# charger.net
KiCad netlist of a schematic drawn in EAGLE
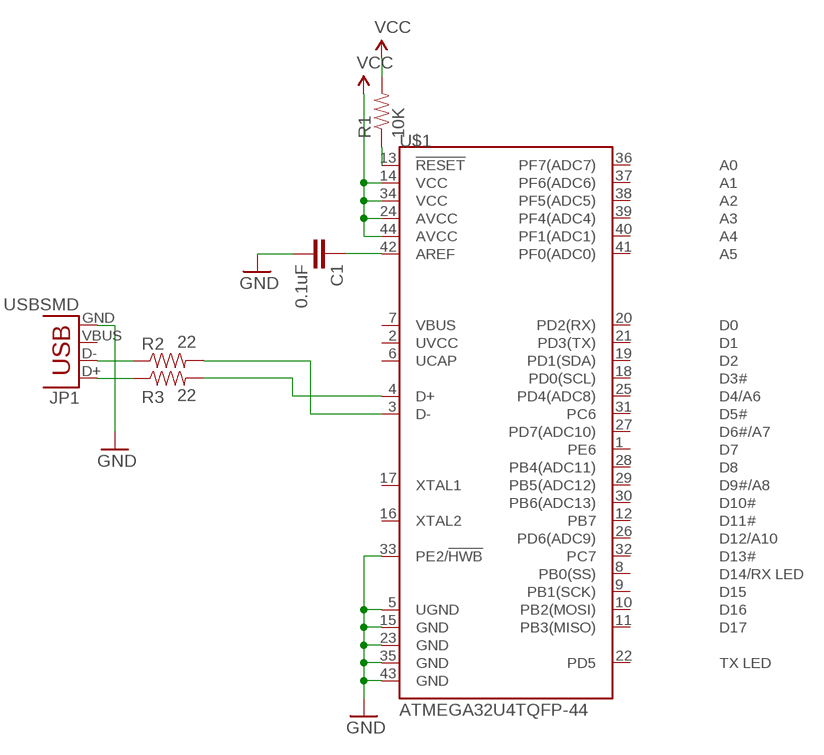
[diagram p0: schematic, sheet 1]

(export (version "E")
  (design (tool "Eeschema 10.0.6"))
  (components
    (comp (ref "C1")
      (value "0.1uF")
      (footprint "eagle-import:0603-CAP")
      (libsource (lib "eagle-import") (part "0.1UF-25V(+80/-20%)(0603)"))
    )
    (comp (ref "JP1")
      (value "USBSMD")
      (footprint "eagle-import:USB-MINIB")
      (libsource (lib "eagle-import") (part "USBSMD"))
    )
    (comp (ref "R1")
      (value "10K")
      (footprint "eagle-import:0603-RES")
      (libsource (lib "eagle-import") (part "10KOHM-1/10W-1%(0603)0603"))
    )
    (comp (ref "R2")
      (value "22")
      (footprint "eagle-import:0603-RES")
      (libsource (lib "eagle-import") (part "22OHM1/10W1%(0603)"))
    )
    (comp (ref "R3")
      (value "22")
      (footprint "eagle-import:0603-RES")
      (libsource (lib "eagle-import") (part "22OHM1/10W1%(0603)"))
    )
    (comp (ref "U$1")
      (value "ATMEGA32U4TQFP-44")
      (footprint "eagle-import:TQFP44")
      (libsource (lib "eagle-import") (part "ATMEGA32U4TQFP-44"))
    )
  )
  (nets
    (net (code "1") (name "GND") (class "Default")
      (node (ref "C1") (pin "2") (pinfunction "2_2") (pintype "passive"))
      (node (ref "JP1") (pin "GND") (pinfunction "GND_GND") (pintype "bidirectional"))
      (node (ref "U$1") (pin "15") (pinfunction "GND_15") (pintype "bidirectional"))
      (node (ref "U$1") (pin "23") (pinfunction "GND_23") (pintype "bidirectional"))
      (node (ref "U$1") (pin "33") (pinfunction "PE2/~{HWB}_33") (pintype "bidirectional"))
      (node (ref "U$1") (pin "35") (pinfunction "GND_35") (pintype "bidirectional"))
      (node (ref "U$1") (pin "43") (pinfunction "GND_43") (pintype "bidirectional"))
      (node (ref "U$1") (pin "5") (pinfunction "UGND_5") (pintype "bidirectional"))
    )
    (net (code "2") (name "Net-(JP1-PadD+)") (class "Default")
      (node (ref "JP1") (pin "D+") (pinfunction "D+_D+") (pintype "bidirectional"))
      (node (ref "R3") (pin "1") (pinfunction "1_1") (pintype "passive"))
    )
    (net (code "3") (name "Net-(JP1-PadD-)") (class "Default")
      (node (ref "JP1") (pin "D-") (pinfunction "D-_D-") (pintype "bidirectional"))
      (node (ref "R2") (pin "1") (pinfunction "1_1") (pintype "passive"))
    )
    (net (code "4") (name "Net-(U$1-AREF)") (class "Default")
      (node (ref "C1") (pin "1") (pinfunction "1_1") (pintype "passive"))
      (node (ref "U$1") (pin "42") (pinfunction "AREF_42") (pintype "bidirectional"))
    )
    (net (code "5") (name "Net-(U$1-D+)") (class "Default")
      (node (ref "R3") (pin "2") (pinfunction "2_2") (pintype "passive"))
      (node (ref "U$1") (pin "4") (pinfunction "D+_4") (pintype "bidirectional"))
    )
    (net (code "6") (name "Net-(U$1-D-)") (class "Default")
      (node (ref "R2") (pin "2") (pinfunction "2_2") (pintype "passive"))
      (node (ref "U$1") (pin "3") (pinfunction "D-_3") (pintype "bidirectional"))
    )
    (net (code "7") (name "Net-(U$1-~{RESET})") (class "Default")
      (node (ref "R1") (pin "1") (pinfunction "1_1") (pintype "passive"))
      (node (ref "U$1") (pin "13") (pinfunction "~{RESET}_13") (pintype "bidirectional"))
    )
    (net (code "8") (name "VCC") (class "Default")
      (node (ref "R1") (pin "2") (pinfunction "2_2") (pintype "passive"))
      (node (ref "U$1") (pin "14") (pinfunction "VCC_14") (pintype "bidirectional"))
      (node (ref "U$1") (pin "24") (pinfunction "AVCC_24") (pintype "bidirectional"))
      (node (ref "U$1") (pin "34") (pinfunction "VCC_34") (pintype "bidirectional"))
      (node (ref "U$1") (pin "44") (pinfunction "AVCC_44") (pintype "bidirectional"))
    )
    (net (code "9") (name "unconnected-(JP1-PadVBUS)") (class "Default")
      (node (ref "JP1") (pin "VBUS") (pinfunction "VBUS_VBUS") (pintype "bidirectional"))
    )
    (net (code "10") (name "unconnected-(U$1-PB0(SS)-Pad8)") (class "Default")
      (node (ref "U$1") (pin "8") (pinfunction "PB0(SS)_8") (pintype "bidirectional"))
    )
    (net (code "11") (name "unconnected-(U$1-PB1(SCK)-Pad9)") (class "Default")
      (node (ref "U$1") (pin "9") (pinfunction "PB1(SCK)_9") (pintype "bidirectional"))
    )
    (net (code "12") (name "unconnected-(U$1-PB2(MOSI)-Pad10)") (class "Default")
      (node (ref "U$1") (pin "10") (pinfunction "PB2(MOSI)_10") (pintype "bidirectional"))
    )
    (net (code "13") (name "unconnected-(U$1-PB3(MISO)-Pad11)") (class "Default")
      (node (ref "U$1") (pin "11") (pinfunction "PB3(MISO)_11") (pintype "bidirectional"))
    )
    (net (code "14") (name "unconnected-(U$1-PB4(ADC11)-Pad28)") (class "Default")
      (node (ref "U$1") (pin "28") (pinfunction "PB4(ADC11)_28") (pintype "bidirectional"))
    )
    (net (code "15") (name "unconnected-(U$1-PB5(ADC12)-Pad29)") (class "Default")
      (node (ref "U$1") (pin "29") (pinfunction "PB5(ADC12)_29") (pintype "bidirectional"))
    )
    (net (code "16") (name "unconnected-(U$1-PB6(ADC13)-Pad30)") (class "Default")
      (node (ref "U$1") (pin "30") (pinfunction "PB6(ADC13)_30") (pintype "bidirectional"))
    )
    (net (code "17") (name "unconnected-(U$1-PB7-Pad12)") (class "Default")
      (node (ref "U$1") (pin "12") (pinfunction "PB7_12") (pintype "bidirectional"))
    )
    (net (code "18") (name "unconnected-(U$1-PC6-Pad31)") (class "Default")
      (node (ref "U$1") (pin "31") (pinfunction "PC6_31") (pintype "bidirectional"))
    )
    (net (code "19") (name "unconnected-(U$1-PC7-Pad32)") (class "Default")
      (node (ref "U$1") (pin "32") (pinfunction "PC7_32") (pintype "bidirectional"))
    )
    (net (code "20") (name "unconnected-(U$1-PD0(SCL)-Pad18)") (class "Default")
      (node (ref "U$1") (pin "18") (pinfunction "PD0(SCL)_18") (pintype "bidirectional"))
    )
    (net (code "21") (name "unconnected-(U$1-PD1(SDA)-Pad19)") (class "Default")
      (node (ref "U$1") (pin "19") (pinfunction "PD1(SDA)_19") (pintype "bidirectional"))
    )
    (net (code "22") (name "unconnected-(U$1-PD2(RX)-Pad20)") (class "Default")
      (node (ref "U$1") (pin "20") (pinfunction "PD2(RX)_20") (pintype "bidirectional"))
    )
    (net (code "23") (name "unconnected-(U$1-PD3(TX)-Pad21)") (class "Default")
      (node (ref "U$1") (pin "21") (pinfunction "PD3(TX)_21") (pintype "bidirectional"))
    )
    (net (code "24") (name "unconnected-(U$1-PD4(ADC8)-Pad25)") (class "Default")
      (node (ref "U$1") (pin "25") (pinfunction "PD4(ADC8)_25") (pintype "bidirectional"))
    )
    (net (code "25") (name "unconnected-(U$1-PD5-Pad22)") (class "Default")
      (node (ref "U$1") (pin "22") (pinfunction "PD5_22") (pintype "bidirectional"))
    )
    (net (code "26") (name "unconnected-(U$1-PD6(ADC9)-Pad26)") (class "Default")
      (node (ref "U$1") (pin "26") (pinfunction "PD6(ADC9)_26") (pintype "bidirectional"))
    )
    (net (code "27") (name "unconnected-(U$1-PD7(ADC10)-Pad27)") (class "Default")
      (node (ref "U$1") (pin "27") (pinfunction "PD7(ADC10)_27") (pintype "bidirectional"))
    )
    (net (code "28") (name "unconnected-(U$1-PE6-Pad1)") (class "Default")
      (node (ref "U$1") (pin "1") (pinfunction "PE6_1") (pintype "bidirectional"))
    )
    (net (code "29") (name "unconnected-(U$1-PF0(ADC0)-Pad41)") (class "Default")
      (node (ref "U$1") (pin "41") (pinfunction "PF0(ADC0)_41") (pintype "bidirectional"))
    )
    (net (code "30") (name "unconnected-(U$1-PF1(ADC1)-Pad40)") (class "Default")
      (node (ref "U$1") (pin "40") (pinfunction "PF1(ADC1)_40") (pintype "bidirectional"))
    )
    (net (code "31") (name "unconnected-(U$1-PF4(ADC4)-Pad39)") (class "Default")
      (node (ref "U$1") (pin "39") (pinfunction "PF4(ADC4)_39") (pintype "bidirectional"))
    )
    (net (code "32") (name "unconnected-(U$1-PF5(ADC5)-Pad38)") (class "Default")
      (node (ref "U$1") (pin "38") (pinfunction "PF5(ADC5)_38") (pintype "bidirectional"))
    )
    (net (code "33") (name "unconnected-(U$1-PF6(ADC6)-Pad37)") (class "Default")
      (node (ref "U$1") (pin "37") (pinfunction "PF6(ADC6)_37") (pintype "bidirectional"))
    )
    (net (code "34") (name "unconnected-(U$1-PF7(ADC7)-Pad36)") (class "Default")
      (node (ref "U$1") (pin "36") (pinfunction "PF7(ADC7)_36") (pintype "bidirectional"))
    )
    (net (code "35") (name "unconnected-(U$1-UCAP-Pad6)") (class "Default")
      (node (ref "U$1") (pin "6") (pinfunction "UCAP_6") (pintype "bidirectional"))
    )
    (net (code "36") (name "unconnected-(U$1-UVCC-Pad2)") (class "Default")
      (node (ref "U$1") (pin "2") (pinfunction "UVCC_2") (pintype "bidirectional"))
    )
    (net (code "37") (name "unconnected-(U$1-VBUS-Pad7)") (class "Default")
      (node (ref "U$1") (pin "7") (pinfunction "VBUS_7") (pintype "bidirectional"))
    )
    (net (code "38") (name "unconnected-(U$1-XTAL1-Pad17)") (class "Default")
      (node (ref "U$1") (pin "17") (pinfunction "XTAL1_17") (pintype "bidirectional"))
    )
    (net (code "39") (name "unconnected-(U$1-XTAL2-Pad16)") (class "Default")
      (node (ref "U$1") (pin "16") (pinfunction "XTAL2_16") (pintype "bidirectional"))
    )
  )
)
